# Mach_Probe.net
KiCad netlist of a schematic drawn in Altium Designer
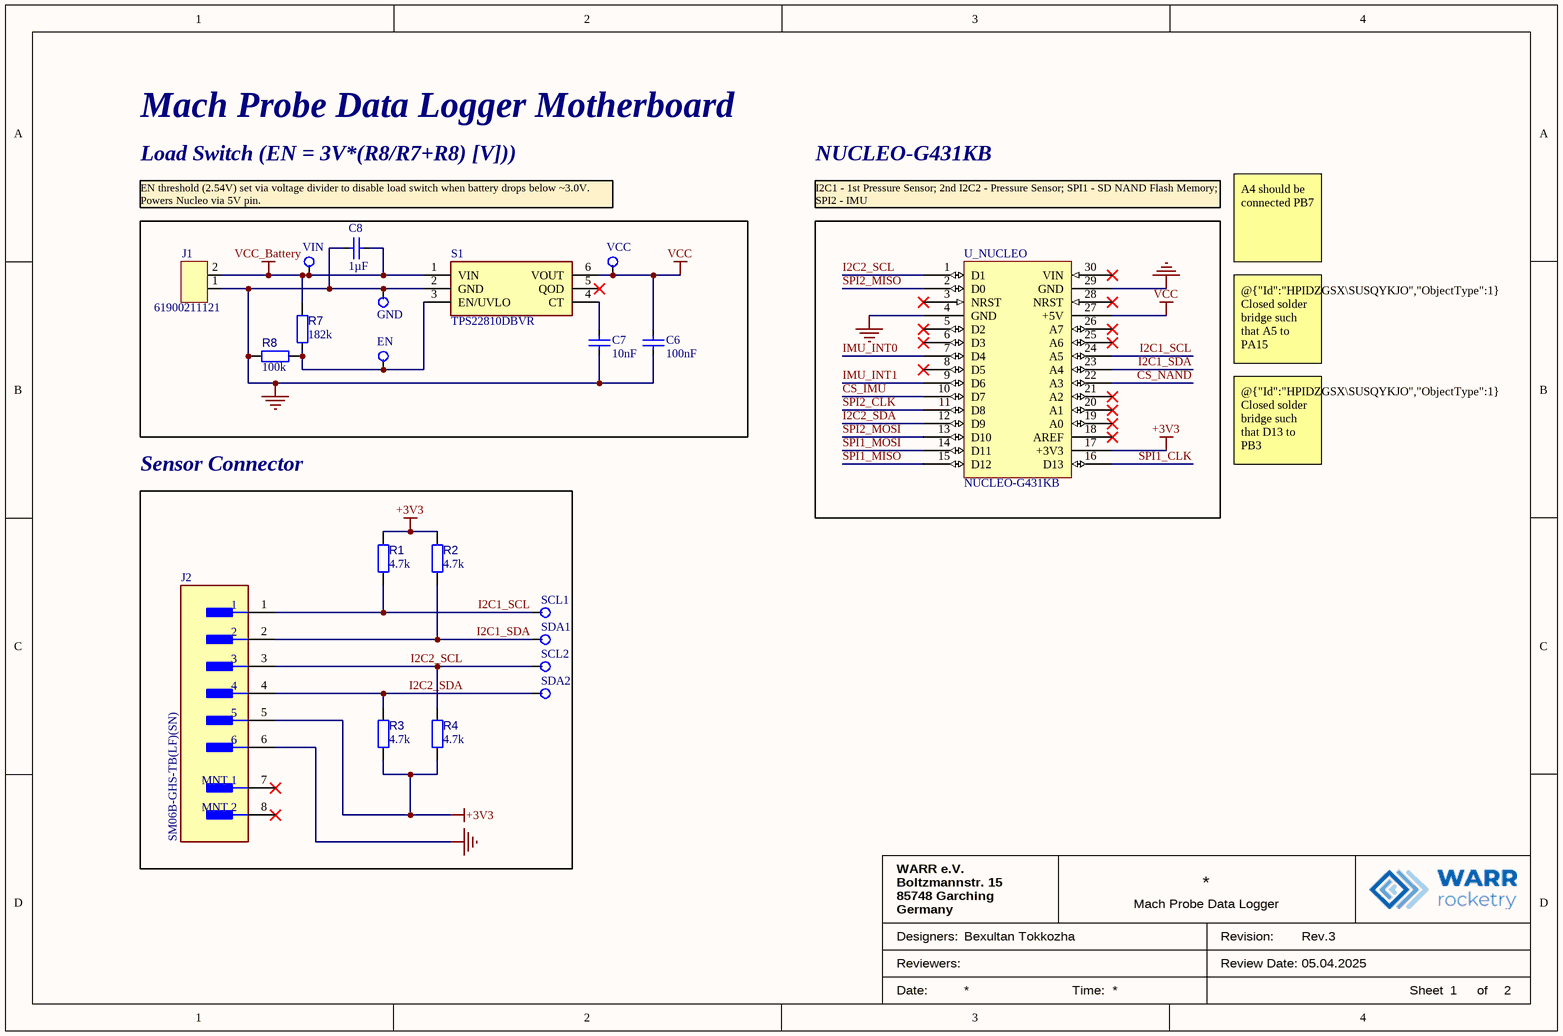
[diagram p0: Mach_Probe.SchDoc]

(export (version "E")
  (design (tool "Eeschema 10.0.6"))
  (components
    (comp (ref "C6")
      (value "100nF")
      (footprint "CAP_0603")
      (fields (field (name "Comment") "C_0603_100n_5%_50V"))
      (libsource (lib "WARR Rocketry Electronics") (part "Capacitor"))
    )
    (comp (ref "C7")
      (value "10nF")
      (footprint "CAP_0603")
      (fields (field (name "TOLERANCE") "5%") (field (name "Comment") "C_0603_10n_5%_50V"))
      (libsource (lib "WARR Rocketry Electronics") (part "Capacitor"))
    )
    (comp (ref "C8")
      (value "1µF")
      (footprint "CAP_0603")
      (description "Ceramic Capacitor, Multilayer, Ceramic, 50V, 10% +Tol, 10% -Tol, 1uF, Surface Mount, 0603")
      (fields (field (name "Comment") "C_0603_1u_10%_50V"))
      (libsource (lib "WARR Rocketry Electronics") (part "Capacitor"))
    )
    (comp (ref "EN")
      (value "Testpoint")
      (footprint "Testpoint-Footprint-1")
      (description "Schematic for Testpoint")
      (libsource (lib "WARR Rocketry Electronics") (part "TP?"))
    )
    (comp (ref "GND")
      (value "Testpoint")
      (footprint "Testpoint-Footprint-1")
      (description "Schematic for Testpoint")
      (libsource (lib "WARR Rocketry Electronics") (part "TP?"))
    )
    (comp (ref "J1")
      (value "61900211121")
      (footprint "61900211121")
      (description "Molex KK 2 Pin")
      (libsource (lib "WARR Rocketry Electronics") (part "61900211121"))
    )
    (comp (ref "J2")
      (value "SM06B-GHS-TB(LF)(SN)")
      (footprint "FP-SM06B-GHS-TB_LF_SN-MFG")
      (description "CONN HEADER SMD R/A 6POS 1.25MM")
      (libsource (lib "Altium Content Vault") (part "ed24c53d9ba001d1a2a686240a95171"))
    )
    (comp (ref "R1")
      (value "4.7k")
      (footprint "RES_0603_YAGEO")
      (fields
        (field (name "POWER") "100mW")
        (field (name "TOLERANCE") "1%")
        (field (name "Comment") "RES_0603_4k7_1%_0.1W")
      )
      (libsource (lib "") (part "RES-2_1"))
    )
    (comp (ref "R2")
      (value "4.7k")
      (footprint "RES_0603_YAGEO")
      (fields
        (field (name "POWER") "100mW")
        (field (name "TOLERANCE") "1%")
        (field (name "Comment") "RES_0603_4k7_1%_0.1W")
      )
      (libsource (lib "") (part "RES-2_1"))
    )
    (comp (ref "R3")
      (value "4.7k")
      (footprint "RES_0603_YAGEO")
      (fields
        (field (name "POWER") "100mW")
        (field (name "TOLERANCE") "1%")
        (field (name "Comment") "RES_0603_4k7_1%_0.1W")
      )
      (libsource (lib "WARR Rocketry Electronics") (part "RES-2"))
    )
    (comp (ref "R4")
      (value "4.7k")
      (footprint "RES_0603_YAGEO")
      (fields
        (field (name "POWER") "100mW")
        (field (name "TOLERANCE") "1%")
        (field (name "Comment") "RES_0603_4k7_1%_0.1W")
      )
      (libsource (lib "WARR Rocketry Electronics") (part "RES-2"))
    )
    (comp (ref "R7")
      (value "182k")
      (footprint "RES_0603_YAGEO")
      (fields
        (field (name "TOLERANCE") "1%")
        (field (name "POWER") "100mW")
        (field (name "Comment") "RES_0603_182k_1%_0.1W")
      )
      (libsource (lib "") (part "RES-2_1"))
    )
    (comp (ref "R8")
      (value "100k")
      (footprint "RES_0603_YAGEO")
      (fields
        (field (name "TOLERANCE") "1%")
        (field (name "POWER") "100mW")
        (field (name "Comment") "RES_0603_100k_1%_0.1W")
      )
      (libsource (lib "WARR Rocketry Electronics") (part "RES-2"))
    )
    (comp (ref "S1")
      (value "TPS22810DBVR")
      (footprint "SamacSys:SOT95P280X145-6N")
      (description "Switch")
      (fields (field (name "MOUSER PART NUMBER") "595-TPS22810DBVR"))
      (libsource (lib "*") (part "TPS22810DBVR"))
    )
    (comp (ref "SCL1")
      (value "Testpoint")
      (footprint "Testpoint-Footprint-1")
      (description "Schematic for Testpoint")
      (libsource (lib "WARR Rocketry Electronics") (part "TP?"))
    )
    (comp (ref "SCL2")
      (value "Testpoint")
      (footprint "Testpoint-Footprint-1")
      (description "Schematic for Testpoint")
      (libsource (lib "WARR Rocketry Electronics") (part "TP?"))
    )
    (comp (ref "SDA1")
      (value "Testpoint")
      (footprint "Testpoint-Footprint-1")
      (description "Schematic for Testpoint")
      (libsource (lib "WARR Rocketry Electronics") (part "TP?"))
    )
    (comp (ref "SDA2")
      (value "Testpoint")
      (footprint "Testpoint-Footprint-1")
      (description "Schematic for Testpoint")
      (libsource (lib "WARR Rocketry Electronics") (part "TP?"))
    )
    (comp (ref "U_NUCLEO")
      (value "NUCLEO-G431KB")
      (footprint "NUCLEO-G431KB-Footprint-1")
      (description "STM32G431 Nucleo-32 Bit ARM Cortex-M4 Microcontroller Evaluation Board")
      (libsource (lib "WARR Rocketry Electronics") (part "NUCLEO-G431KB-Symbol-1"))
    )
    (comp (ref "VCC")
      (value "Testpoint")
      (footprint "Testpoint-Footprint-1")
      (description "Schematic for Testpoint")
      (libsource (lib "WARR Rocketry Electronics") (part "TP?"))
    )
    (comp (ref "VIN")
      (value "Testpoint")
      (footprint "Testpoint-Footprint-1")
      (description "Schematic for Testpoint")
      (libsource (lib "WARR Rocketry Electronics") (part "TP?"))
    )
  )
  (nets
    (net (code "1") (name "+3V3") (class "Default")
      (node (ref "J2") (pin "5") (pinfunction "5_5") (pintype "passive"))
      (node (ref "R1") (pin "2") (pinfunction "2_2") (pintype "passive"))
      (node (ref "R2") (pin "2") (pinfunction "2_2") (pintype "passive"))
      (node (ref "R3") (pin "2") (pinfunction "2_2") (pintype "passive"))
      (node (ref "R4") (pin "2") (pinfunction "2_2") (pintype "passive"))
      (node (ref "U_NUCLEO") (pin "17") (pinfunction "+3V3_17") (pintype "power_in"))
    )
    (net (code "2") (name "/CS_IMU") (class "Default")
      (node (ref "U_NUCLEO") (pin "10") (pinfunction "D7_10") (pintype "bidirectional"))
    )
    (net (code "3") (name "/CS_NAND") (class "Default")
      (node (ref "U_NUCLEO") (pin "22") (pinfunction "A3_22") (pintype "bidirectional"))
    )
    (net (code "4") (name "/I2C1_SCL") (class "Default")
      (node (ref "J2") (pin "1") (pinfunction "1_1") (pintype "passive"))
      (node (ref "R1") (pin "1") (pinfunction "1_1") (pintype "passive"))
      (node (ref "SCL1") (pin "1") (pinfunction "1_1") (pintype "passive"))
      (node (ref "U_NUCLEO") (pin "24") (pinfunction "A5_24") (pintype "bidirectional"))
    )
    (net (code "5") (name "/I2C1_SDA") (class "Default")
      (node (ref "J2") (pin "2") (pinfunction "2_2") (pintype "passive"))
      (node (ref "R2") (pin "1") (pinfunction "1_1") (pintype "passive"))
      (node (ref "SDA1") (pin "1") (pinfunction "1_1") (pintype "passive"))
      (node (ref "U_NUCLEO") (pin "23") (pinfunction "A4_23") (pintype "bidirectional"))
    )
    (net (code "6") (name "/I2C2_SCL") (class "Default")
      (node (ref "J2") (pin "3") (pinfunction "3_3") (pintype "passive"))
      (node (ref "R4") (pin "1") (pinfunction "1_1") (pintype "passive"))
      (node (ref "SCL2") (pin "1") (pinfunction "1_1") (pintype "passive"))
      (node (ref "U_NUCLEO") (pin "1") (pinfunction "D1_1") (pintype "bidirectional"))
    )
    (net (code "7") (name "/I2C2_SDA") (class "Default")
      (node (ref "J2") (pin "4") (pinfunction "4_4") (pintype "passive"))
      (node (ref "R3") (pin "1") (pinfunction "1_1") (pintype "passive"))
      (node (ref "SDA2") (pin "1") (pinfunction "1_1") (pintype "passive"))
      (node (ref "U_NUCLEO") (pin "12") (pinfunction "D9_12") (pintype "bidirectional"))
    )
    (net (code "8") (name "/IMU_INT0") (class "Default")
      (node (ref "U_NUCLEO") (pin "7") (pinfunction "D4_7") (pintype "bidirectional"))
    )
    (net (code "9") (name "/IMU_INT1") (class "Default")
      (node (ref "U_NUCLEO") (pin "9") (pinfunction "D6_9") (pintype "bidirectional"))
    )
    (net (code "10") (name "/SPI1_CLK") (class "Default")
      (node (ref "U_NUCLEO") (pin "16") (pinfunction "D13_16") (pintype "bidirectional"))
    )
    (net (code "11") (name "/SPI1_MISO") (class "Default")
      (node (ref "U_NUCLEO") (pin "15") (pinfunction "D12_15") (pintype "bidirectional"))
    )
    (net (code "12") (name "/SPI1_MOSI") (class "Default")
      (node (ref "U_NUCLEO") (pin "14") (pinfunction "D11_14") (pintype "bidirectional"))
    )
    (net (code "13") (name "/SPI2_CLK") (class "Default")
      (node (ref "U_NUCLEO") (pin "11") (pinfunction "D8_11") (pintype "bidirectional"))
    )
    (net (code "14") (name "/SPI2_MISO") (class "Default")
      (node (ref "U_NUCLEO") (pin "2") (pinfunction "D0_2") (pintype "bidirectional"))
    )
    (net (code "15") (name "/SPI2_MOSI") (class "Default")
      (node (ref "U_NUCLEO") (pin "13") (pinfunction "D10_13") (pintype "bidirectional"))
    )
    (net (code "16") (name "GND") (class "Default")
      (node (ref "C6") (pin "2") (pinfunction "2_2") (pintype "passive"))
      (node (ref "C7") (pin "2") (pinfunction "2_2") (pintype "passive"))
      (node (ref "C8") (pin "1") (pinfunction "1_1") (pintype "passive"))
      (node (ref "GND") (pin "1") (pinfunction "1_1") (pintype "passive"))
      (node (ref "J1") (pin "1") (pinfunction "=Designator_1") (pintype "passive"))
      (node (ref "J2") (pin "6") (pinfunction "6_6") (pintype "passive"))
      (node (ref "R8") (pin "2") (pinfunction "2_2") (pintype "passive"))
      (node (ref "S1") (pin "2") (pinfunction "GND_2") (pintype "passive"))
      (node (ref "U_NUCLEO") (pin "29") (pinfunction "GND_29") (pintype "power_in"))
      (node (ref "U_NUCLEO") (pin "4") (pinfunction "GND_4") (pintype "power_in"))
    )
    (net (code "17") (name "Net-(S1-CT)") (class "Default")
      (node (ref "C7") (pin "1") (pinfunction "1_1") (pintype "passive"))
      (node (ref "S1") (pin "4") (pinfunction "CT_4") (pintype "passive"))
    )
    (net (code "18") (name "Net-(S1-EN{slash}UVLO)") (class "Default")
      (node (ref "EN") (pin "1") (pinfunction "1_1") (pintype "passive"))
      (node (ref "R7") (pin "1") (pinfunction "1_1") (pintype "passive"))
      (node (ref "R8") (pin "1") (pinfunction "1_1") (pintype "passive"))
      (node (ref "S1") (pin "3") (pinfunction "EN/UVLO_3") (pintype "passive"))
    )
    (net (code "19") (name "VCC") (class "Default")
      (node (ref "C6") (pin "1") (pinfunction "1_1") (pintype "passive"))
      (node (ref "S1") (pin "6") (pinfunction "VOUT_6") (pintype "passive"))
      (node (ref "U_NUCLEO") (pin "27") (pinfunction "+5V_27") (pintype "power_in"))
      (node (ref "VCC") (pin "1") (pinfunction "1_1") (pintype "passive"))
    )
    (net (code "20") (name "VCC_Battery") (class "Default")
      (node (ref "C8") (pin "2") (pinfunction "2_2") (pintype "passive"))
      (node (ref "J1") (pin "2") (pinfunction "=Designator_2") (pintype "passive"))
      (node (ref "R7") (pin "2") (pinfunction "2_2") (pintype "passive"))
      (node (ref "S1") (pin "1") (pinfunction "VIN_1") (pintype "passive"))
      (node (ref "VIN") (pin "1") (pinfunction "1_1") (pintype "passive"))
    )
    (net (code "21") (name "unconnected-(J2-MNT_1-Pad7)") (class "Default")
      (node (ref "J2") (pin "7") (pinfunction "MNT_1_7") (pintype "passive+no_connect"))
    )
    (net (code "22") (name "unconnected-(J2-MNT_2-Pad8)") (class "Default")
      (node (ref "J2") (pin "8") (pinfunction "MNT_2_8") (pintype "passive+no_connect"))
    )
    (net (code "23") (name "unconnected-(S1-QOD-Pad5)") (class "Default")
      (node (ref "S1") (pin "5") (pinfunction "QOD_5") (pintype "passive+no_connect"))
    )
    (net (code "24") (name "unconnected-(U_NUCLEO-A0-Pad19)") (class "Default")
      (node (ref "U_NUCLEO") (pin "19") (pinfunction "A0_19") (pintype "bidirectional+no_connect"))
    )
    (net (code "25") (name "unconnected-(U_NUCLEO-A1-Pad20)") (class "Default")
      (node (ref "U_NUCLEO") (pin "20") (pinfunction "A1_20") (pintype "bidirectional+no_connect"))
    )
    (net (code "26") (name "unconnected-(U_NUCLEO-A2-Pad21)") (class "Default")
      (node (ref "U_NUCLEO") (pin "21") (pinfunction "A2_21") (pintype "bidirectional+no_connect"))
    )
    (net (code "27") (name "unconnected-(U_NUCLEO-A6-Pad25)") (class "Default")
      (node (ref "U_NUCLEO") (pin "25") (pinfunction "A6_25") (pintype "bidirectional+no_connect"))
    )
    (net (code "28") (name "unconnected-(U_NUCLEO-A7-Pad26)") (class "Default")
      (node (ref "U_NUCLEO") (pin "26") (pinfunction "A7_26") (pintype "bidirectional+no_connect"))
    )
    (net (code "29") (name "unconnected-(U_NUCLEO-AREF-Pad18)") (class "Default")
      (node (ref "U_NUCLEO") (pin "18") (pinfunction "AREF_18") (pintype "power_in+no_connect"))
    )
    (net (code "30") (name "unconnected-(U_NUCLEO-D2-Pad5)") (class "Default")
      (node (ref "U_NUCLEO") (pin "5") (pinfunction "D2_5") (pintype "bidirectional+no_connect"))
    )
    (net (code "31") (name "unconnected-(U_NUCLEO-D3-Pad6)") (class "Default")
      (node (ref "U_NUCLEO") (pin "6") (pinfunction "D3_6") (pintype "bidirectional+no_connect"))
    )
    (net (code "32") (name "unconnected-(U_NUCLEO-D5-Pad8)") (class "Default")
      (node (ref "U_NUCLEO") (pin "8") (pinfunction "D5_8") (pintype "bidirectional+no_connect"))
    )
    (net (code "33") (name "unconnected-(U_NUCLEO-NRST-Pad3)") (class "Default")
      (node (ref "U_NUCLEO") (pin "3") (pinfunction "NRST_3") (pintype "input+no_connect"))
    )
    (net (code "34") (name "unconnected-(U_NUCLEO-NRST-Pad28)") (class "Default")
      (node (ref "U_NUCLEO") (pin "28") (pinfunction "NRST_28") (pintype "input+no_connect"))
    )
    (net (code "35") (name "unconnected-(U_NUCLEO-VIN-Pad30)") (class "Default")
      (node (ref "U_NUCLEO") (pin "30") (pinfunction "VIN_30") (pintype "input+no_connect"))
    )
  )
)
